# Power.net
KiCad netlist of a schematic drawn in Altium Designer
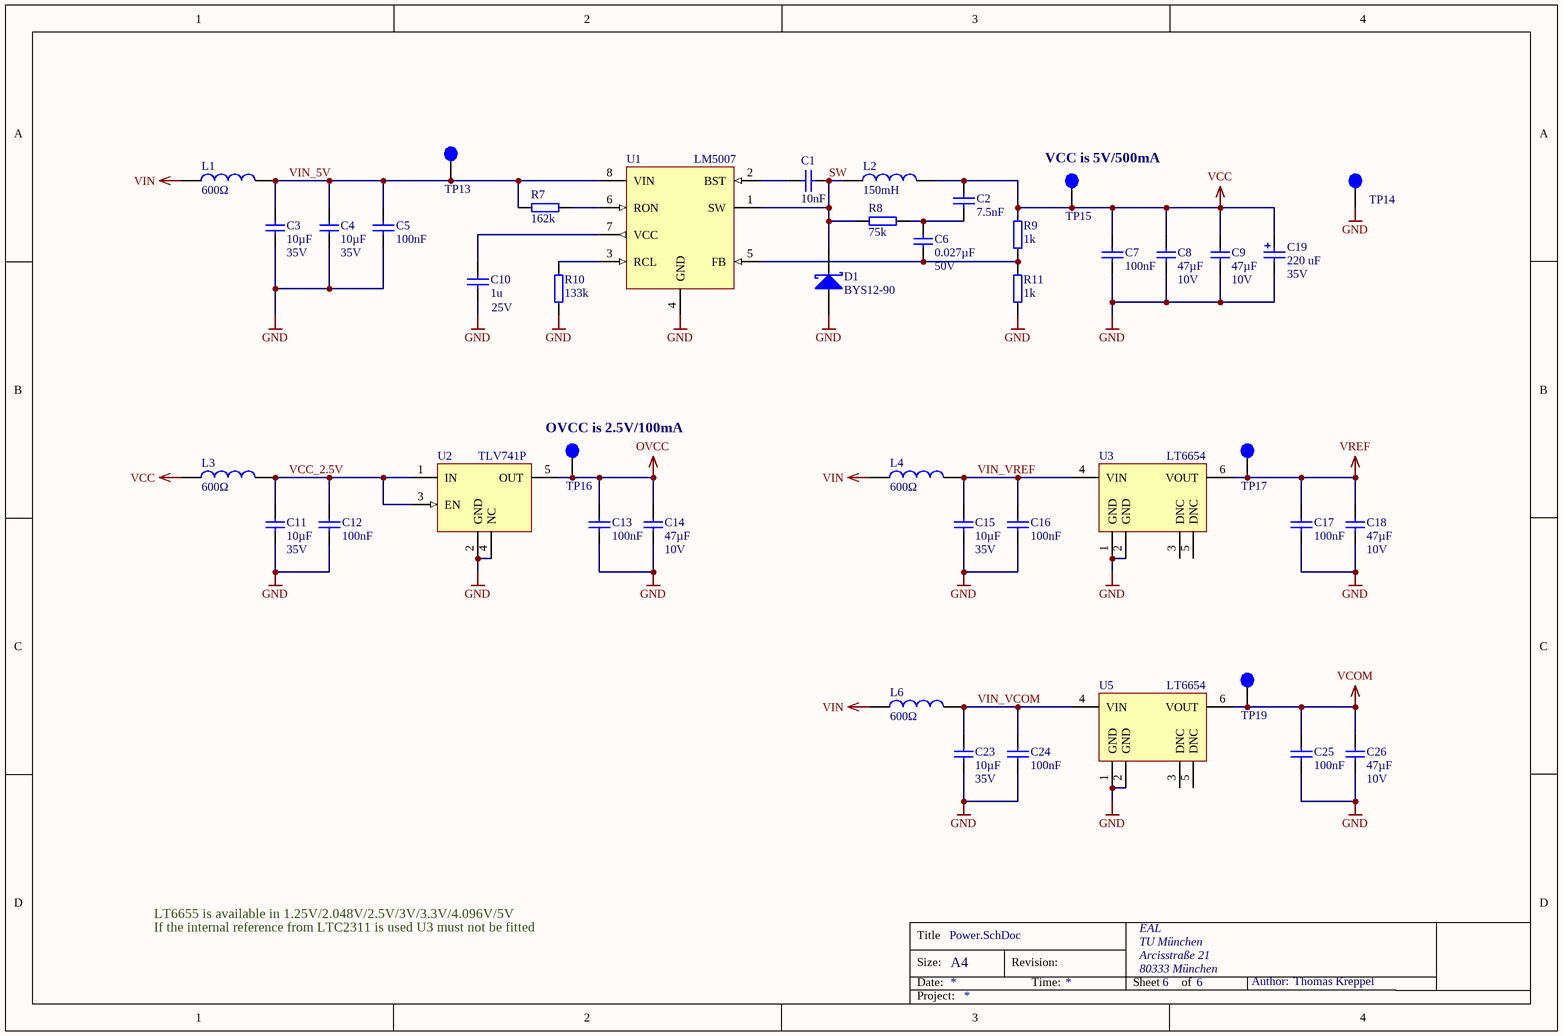
[diagram p0: Power.SchDoc]

(export (version "E")
  (design (tool "Eeschema 10.0.6"))
  (components
    (comp (ref "C1")
      (value "10nF")
      (footprint "CAPC1608X07N")
      (fields (field (name "MF") "Würth") (field (name "MPN") "885012206065") (field (name "VOLTAGE") "25V"))
      (libsource (lib "UltraZohm_ADC") (part "Cap_0603"))
    )
    (comp (ref "C2")
      (value "7.5nF")
      (footprint "CAPC1608X07N")
      (fields
        (field (name "MF") "KEMET")
        (field (name "MPN") "C0603C752J3GACTU")
        (field (name "VOLTAGE") "25V")
      )
      (libsource (lib "UltraZohm_ADC") (part "Cap_0603"))
    )
    (comp (ref "C3")
      (value "10µF")
      (footprint "C_1206")
      (description "Capacitor 1206")
      (fields
        (field (name "TOLERANCE") "10%")
        (field (name "MF") "Murata Electronics")
        (field (name "VOLTAGE") "35V")
        (field (name "CREATED") "2018_06_25_AGeiger")
      )
      (libsource (lib "UltraZohm_ADC") (part "C_1206"))
    )
    (comp (ref "C4")
      (value "10µF")
      (footprint "C_1206")
      (description "Capacitor 1206")
      (fields
        (field (name "TOLERANCE") "10%")
        (field (name "MF") "Murata Electronics")
        (field (name "VOLTAGE") "35V")
        (field (name "CREATED") "2018_06_25_AGeiger")
      )
      (libsource (lib "UltraZohm_ADC") (part "C_1206"))
    )
    (comp (ref "C5")
      (value "100nF")
      (footprint "CAPC1608X07N")
      (fields (field (name "MF") "Würth") (field (name "MPN") "885012206071") (field (name "VOLTAGE") "25V"))
      (libsource (lib "UltraZohm_ADC") (part "Cap_0603"))
    )
    (comp (ref "C6")
      (value "0.027µF")
      (footprint "C_1206")
      (description "Capacitor 1206")
      (fields
        (field (name "TOLERANCE") "5%")
        (field (name "MF") "Murata")
        (field (name "VOLTAGE") "50V")
        (field (name "CREATED") "2018_06_25_AGeiger")
      )
      (libsource (lib "UltraZohm_ADC") (part "C_1206"))
    )
    (comp (ref "C7")
      (value "100nF")
      (footprint "CAPC1608X07N")
      (fields (field (name "MF") "Würth") (field (name "MPN") "885012206071") (field (name "VOLTAGE") "25V"))
      (libsource (lib "UltraZohm_ADC") (part "Cap_0603"))
    )
    (comp (ref "C8")
      (value "47µF")
      (footprint "C_1206")
      (description "Capacitor 1206")
      (fields
        (field (name "TOLERANCE") "10%")
        (field (name "MF") "Murata Electronics")
        (field (name "VOLTAGE") "10V")
        (field (name "CREATED") "2018_06_25_AGeiger")
      )
      (libsource (lib "UltraZohm_ADC") (part "C_1206"))
    )
    (comp (ref "C9")
      (value "47µF")
      (footprint "C_1206")
      (description "Capacitor 1206")
      (fields
        (field (name "TOLERANCE") "10%")
        (field (name "MF") "Murata Electronics")
        (field (name "VOLTAGE") "10V")
        (field (name "CREATED") "2018_06_25_AGeiger")
      )
      (libsource (lib "UltraZohm_ADC") (part "C_1206"))
    )
    (comp (ref "C10")
      (value "1u")
      (footprint "CAPC1608X07N")
      (fields (field (name "MF") "Würth") (field (name "MPN") "885012106022") (field (name "VOLTAGE") "25V"))
      (libsource (lib "UltraZohm_ADC") (part "Cap_0603"))
    )
    (comp (ref "C11")
      (value "10µF")
      (footprint "C_1206")
      (description "Capacitor 1206")
      (fields
        (field (name "TOLERANCE") "10%")
        (field (name "MF") "Murata Electronics")
        (field (name "VOLTAGE") "35V")
        (field (name "CREATED") "2018_06_25_AGeiger")
      )
      (libsource (lib "UltraZohm_ADC") (part "C_1206"))
    )
    (comp (ref "C12")
      (value "100nF")
      (footprint "CAPC1608X07N")
      (fields (field (name "MF") "Würth") (field (name "MPN") "885012206071") (field (name "VOLTAGE") "25V"))
      (libsource (lib "UltraZohm_ADC") (part "Cap_0603"))
    )
    (comp (ref "C13")
      (value "100nF")
      (footprint "CAPC1608X07N")
      (fields (field (name "MF") "Würth") (field (name "MPN") "885012206071") (field (name "VOLTAGE") "25V"))
      (libsource (lib "UltraZohm_ADC") (part "Cap_0603"))
    )
    (comp (ref "C14")
      (value "47µF")
      (footprint "C_1206")
      (description "Capacitor 1206")
      (fields
        (field (name "TOLERANCE") "10%")
        (field (name "MF") "Murata Electronics")
        (field (name "VOLTAGE") "10V")
        (field (name "CREATED") "2018_06_25_AGeiger")
      )
      (libsource (lib "UltraZohm_ADC") (part "C_1206"))
    )
    (comp (ref "C15")
      (value "10µF")
      (footprint "C_1206")
      (description "Capacitor 1206")
      (fields
        (field (name "TOLERANCE") "10%")
        (field (name "MF") "Murata Electronics")
        (field (name "VOLTAGE") "35V")
        (field (name "CREATED") "2018_06_25_AGeiger")
      )
      (libsource (lib "UltraZohm_ADC") (part "C_1206"))
    )
    (comp (ref "C16")
      (value "100nF")
      (footprint "CAPC1608X07N")
      (fields (field (name "MF") "Würth") (field (name "MPN") "885012206071") (field (name "VOLTAGE") "25V"))
      (libsource (lib "UltraZohm_ADC") (part "Cap_0603"))
    )
    (comp (ref "C17")
      (value "100nF")
      (footprint "CAPC1608X07N")
      (fields (field (name "MF") "Würth") (field (name "MPN") "885012206071") (field (name "VOLTAGE") "25V"))
      (libsource (lib "UltraZohm_ADC") (part "Cap_0603"))
    )
    (comp (ref "C18")
      (value "47µF")
      (footprint "C_1206")
      (description "Capacitor 1206")
      (fields
        (field (name "TOLERANCE") "10%")
        (field (name "MF") "Murata Electronics")
        (field (name "VOLTAGE") "10V")
        (field (name "CREATED") "2018_06_25_AGeiger")
      )
      (libsource (lib "UltraZohm_ADC") (part "C_1206"))
    )
    (comp (ref "C19")
      (value "220 uF")
      (footprint "WCAP-ATG5_8x11.5x3.5")
      (description "WCAP-ATG5 Aluminum Electrolytic Capacitors, 8x11.5mm, 35 Vdc, 220 uF")
      (fields
        (field (name "PART NUMBER") "860020574012")
        (field (name "MF") "Wurth Elektronik")
        (field (name "VOLTAGE") "35V")
      )
      (libsource (lib "UltraZohm_ADC") (part "860020574012"))
    )
    (comp (ref "C23")
      (value "10µF")
      (footprint "C_1206")
      (description "Capacitor 1206")
      (fields
        (field (name "TOLERANCE") "10%")
        (field (name "MF") "Murata Electronics")
        (field (name "VOLTAGE") "35V")
        (field (name "CREATED") "2018_06_25_AGeiger")
      )
      (libsource (lib "UltraZohm_ADC") (part "C_1206"))
    )
    (comp (ref "C24")
      (value "100nF")
      (footprint "CAPC1608X07N")
      (fields (field (name "MF") "Würth") (field (name "MPN") "885012206071") (field (name "VOLTAGE") "25V"))
      (libsource (lib "UltraZohm_ADC") (part "Cap_0603"))
    )
    (comp (ref "C25")
      (value "100nF")
      (footprint "CAPC1608X07N")
      (fields (field (name "MF") "Würth") (field (name "MPN") "885012206071") (field (name "VOLTAGE") "25V"))
      (libsource (lib "UltraZohm_ADC") (part "Cap_0603"))
    )
    (comp (ref "C26")
      (value "47µF")
      (footprint "C_1206")
      (description "Capacitor 1206")
      (fields
        (field (name "TOLERANCE") "10%")
        (field (name "MF") "Murata Electronics")
        (field (name "VOLTAGE") "10V")
        (field (name "CREATED") "2018_06_25_AGeiger")
      )
      (libsource (lib "UltraZohm_ADC") (part "C_1206"))
    )
    (comp (ref "D1")
      (value "BYS12-90")
      (footprint "DIOM4227X23N")
      (description "Schottky Diode")
      (fields (field (name "MF") "Vishay") (field (name "MPN") "BYS12-90-E3/TR3"))
      (libsource (lib "UltraZohm_ADC") (part "BYS12-90"))
    )
    (comp (ref "L1")
      (value "600Ω")
      (footprint "WE-CBF_0805_High Current")
      (description "WE-CBF SMD EMI Suppression Ferrite Bead, 0805, 600Ω")
      (fields (field (name "MF") "Wurth Elektronik") (field (name "MPN") "742792040"))
      (libsource (lib "UltraZohm_ADC") (part "WE-CBF, 742792040"))
    )
    (comp (ref "L2")
      (value "150mH")
      (footprint "SMT_inductor_1050_Performance")
      (description "SMT power Inductor, 150uH, 320m DRC")
      (fields (field (name "MF") "EPCOS / TDK") (field (name "MPN") "B82464G4154M"))
      (libsource (lib "UltraZohm_ADC") (part "B82464G4154M"))
    )
    (comp (ref "L3")
      (value "600Ω")
      (footprint "WE-CBF_0805_High Current")
      (description "WE-CBF SMD EMI Suppression Ferrite Bead, 0805, 600Ω")
      (fields (field (name "MF") "Wurth Elektronik") (field (name "MPN") "742792040"))
      (libsource (lib "UltraZohm_ADC") (part "WE-CBF, 742792040"))
    )
    (comp (ref "L4")
      (value "600Ω")
      (footprint "WE-CBF_0805_High Current")
      (description "WE-CBF SMD EMI Suppression Ferrite Bead, 0805, 600Ω")
      (fields (field (name "MF") "Wurth Elektronik") (field (name "MPN") "742792040"))
      (libsource (lib "UltraZohm_ADC") (part "WE-CBF, 742792040"))
    )
    (comp (ref "L6")
      (value "600Ω")
      (footprint "WE-CBF_0805_High Current")
      (description "WE-CBF SMD EMI Suppression Ferrite Bead, 0805, 600Ω")
      (fields (field (name "MF") "Wurth Elektronik") (field (name "MPN") "742792040"))
      (libsource (lib "UltraZohm_ADC") (part "WE-CBF, 742792040"))
    )
    (comp (ref "R7")
      (value "162k")
      (footprint "RESC1608X06N")
      (fields (field (name "MF") "Bourns") (field (name "MPN") "CR0603-FX-1623ELF"))
      (libsource (lib "UltraZohm_ADC") (part "R_0603"))
    )
    (comp (ref "R8")
      (value "75k")
      (footprint "RESC1608X06N")
      (fields (field (name "MF") "Yageo") (field (name "MPN") "AC0603FR-1375KL"))
      (libsource (lib "UltraZohm_ADC") (part "R_0603"))
    )
    (comp (ref "R9")
      (value "1k")
      (footprint "RESC1608X06N")
      (fields (field (name "MF") "Vishay / Dale") (field (name "MPN") "CRCW06031K00JNEAC"))
      (libsource (lib "UltraZohm_ADC") (part "R_0603"))
    )
    (comp (ref "R10")
      (value "133k")
      (footprint "RESC1608X06N")
      (fields (field (name "MF") "Bourns") (field (name "MPN") "CR0603-FX-1333ELF"))
      (libsource (lib "UltraZohm_ADC") (part "R_0603"))
    )
    (comp (ref "R11")
      (value "1k")
      (footprint "RESC1608X06N")
      (fields (field (name "MF") "Vishay / Dale") (field (name "MPN") "CRCW06031K00JNEAC"))
      (libsource (lib "UltraZohm_ADC") (part "R_0603"))
    )
    (comp (ref "TP13")
      (value "VIN")
      (footprint "TP_1mm")
      (description "Testpoint 1mm")
      (fields (field (name "CREATED") "2018_06_25_AGeiger"))
      (libsource (lib "UltraZOhm_CarrierBoard") (part "TP_1mm"))
    )
    (comp (ref "TP14")
      (value "GND")
      (footprint "TP_1mm")
      (description "Testpoint 1mm")
      (fields (field (name "CREATED") "2018_06_25_AGeiger"))
      (libsource (lib "UltraZOhm_CarrierBoard") (part "TP_1mm"))
    )
    (comp (ref "TP15")
      (value "VCC")
      (footprint "TP_1mm")
      (description "Testpoint 1mm")
      (fields (field (name "CREATED") "2018_06_25_AGeiger"))
      (libsource (lib "UltraZOhm_CarrierBoard") (part "TP_1mm"))
    )
    (comp (ref "TP16")
      (value "OVCC")
      (footprint "TP_1mm")
      (description "Testpoint 1mm")
      (fields (field (name "CREATED") "2018_06_25_AGeiger"))
      (libsource (lib "UltraZOhm_CarrierBoard") (part "TP_1mm"))
    )
    (comp (ref "TP17")
      (value "VREF")
      (footprint "TP_1mm")
      (description "Testpoint 1mm")
      (fields (field (name "CREATED") "2018_06_25_AGeiger"))
      (libsource (lib "UltraZOhm_CarrierBoard") (part "TP_1mm"))
    )
    (comp (ref "TP19")
      (value "VCOM")
      (footprint "TP_1mm")
      (description "Testpoint 1mm")
      (fields (field (name "CREATED") "2018_06_25_AGeiger"))
      (libsource (lib "UltraZOhm_CarrierBoard") (part "TP_1mm"))
    )
    (comp (ref "U1")
      (value "LM5007")
      (footprint "TSOP65P490X110-8N")
      (description "Buck Converter, 9-75Vin, 2.5-73Vout")
      (fields (field (name "MF") "Texas Instruments") (field (name "MPN") "LM5007MM/NOPB"))
      (libsource (lib "UltraZohm_ADC") (part "LM5007"))
    )
    (comp (ref "U2")
      (value "TLV741P")
      (footprint "SOT95P250X110-5N")
      (description "150mA, 2.5V LDO")
      (fields (field (name "MF") "Texas Instruments") (field (name "MPN") "TLV74125PDBVR"))
      (libsource (lib "UltraZohm_ADC") (part "TLV741P"))
    )
    (comp (ref "U3")
      (value "LT6654")
      (footprint "SOT95P280X100-6N")
      (fields (field (name "MF") "Analog Devices") (field (name "MPN") "LT6654AIS6-5#TRMPBF"))
      (libsource (lib "UltraZohm_ADC") (part "LT6654"))
    )
    (comp (ref "U5")
      (value "LT6654")
      (footprint "SOT95P280X100-6N")
      (fields (field (name "MF") "Analog Devices") (field (name "MPN") "LT6654AIS6-5#TRMPBF"))
      (libsource (lib "UltraZohm_ADC") (part "LT6654"))
    )
  )
  (nets
    (net (code "1") (name "/SW") (class "Default")
      (node (ref "C1") (pin "2") (pinfunction "2_2") (pintype "passive"))
      (node (ref "D1") (pin "1") (pinfunction "K_1") (pintype "passive"))
      (node (ref "L2") (pin "1") (pinfunction "1_1") (pintype "passive"))
      (node (ref "R8") (pin "1") (pintype "passive"))
      (node (ref "U1") (pin "1") (pinfunction "SW_1") (pintype "power_in"))
    )
    (net (code "2") (name "/VCC_2.5V") (class "Default")
      (node (ref "C11") (pin "2") (pinfunction "2_2") (pintype "passive"))
      (node (ref "C12") (pin "1") (pinfunction "1_1") (pintype "passive"))
      (node (ref "L3") (pin "2") (pinfunction "2_2") (pintype "passive"))
      (node (ref "U2") (pin "1") (pinfunction "IN_1") (pintype "power_in"))
      (node (ref "U2") (pin "3") (pinfunction "EN_3") (pintype "input"))
    )
    (net (code "3") (name "/VIN_5V") (class "Default")
      (node (ref "C3") (pin "2") (pinfunction "2_2") (pintype "passive"))
      (node (ref "C4") (pin "2") (pinfunction "2_2") (pintype "passive"))
      (node (ref "C5") (pin "1") (pinfunction "1_1") (pintype "passive"))
      (node (ref "L1") (pin "2") (pinfunction "2_2") (pintype "passive"))
      (node (ref "R7") (pin "1") (pintype "passive"))
      (node (ref "TP13") (pin "1") (pintype "passive"))
      (node (ref "U1") (pin "8") (pinfunction "VIN_8") (pintype "power_in"))
    )
    (net (code "4") (name "/VIN_VCOM") (class "Default")
      (node (ref "C23") (pin "2") (pinfunction "2_2") (pintype "passive"))
      (node (ref "C24") (pin "1") (pinfunction "1_1") (pintype "passive"))
      (node (ref "L6") (pin "2") (pinfunction "2_2") (pintype "passive"))
      (node (ref "U5") (pin "4") (pinfunction "VIN_4") (pintype "power_in"))
    )
    (net (code "5") (name "/VIN_VREF") (class "Default")
      (node (ref "C15") (pin "2") (pinfunction "2_2") (pintype "passive"))
      (node (ref "C16") (pin "1") (pinfunction "1_1") (pintype "passive"))
      (node (ref "L4") (pin "2") (pinfunction "2_2") (pintype "passive"))
      (node (ref "U3") (pin "4") (pinfunction "VIN_4") (pintype "power_in"))
    )
    (net (code "6") (name "GND") (class "Default")
      (node (ref "C10") (pin "2") (pinfunction "2_2") (pintype "passive"))
      (node (ref "C11") (pin "1") (pinfunction "1_1") (pintype "passive"))
      (node (ref "C12") (pin "2") (pinfunction "2_2") (pintype "passive"))
      (node (ref "C13") (pin "2") (pinfunction "2_2") (pintype "passive"))
      (node (ref "C14") (pin "1") (pinfunction "1_1") (pintype "passive"))
      (node (ref "C15") (pin "1") (pinfunction "1_1") (pintype "passive"))
      (node (ref "C16") (pin "2") (pinfunction "2_2") (pintype "passive"))
      (node (ref "C17") (pin "2") (pinfunction "2_2") (pintype "passive"))
      (node (ref "C18") (pin "1") (pinfunction "1_1") (pintype "passive"))
      (node (ref "C19") (pin "2") (pinfunction "N_2") (pintype "passive"))
      (node (ref "C23") (pin "1") (pinfunction "1_1") (pintype "passive"))
      (node (ref "C24") (pin "2") (pinfunction "2_2") (pintype "passive"))
      (node (ref "C25") (pin "2") (pinfunction "2_2") (pintype "passive"))
      (node (ref "C26") (pin "1") (pinfunction "1_1") (pintype "passive"))
      (node (ref "C3") (pin "1") (pinfunction "1_1") (pintype "passive"))
      (node (ref "C4") (pin "1") (pinfunction "1_1") (pintype "passive"))
      (node (ref "C5") (pin "2") (pinfunction "2_2") (pintype "passive"))
      (node (ref "C7") (pin "1") (pinfunction "1_1") (pintype "passive"))
      (node (ref "C8") (pin "1") (pinfunction "1_1") (pintype "passive"))
      (node (ref "C9") (pin "1") (pinfunction "1_1") (pintype "passive"))
      (node (ref "D1") (pin "2") (pinfunction "A_2") (pintype "passive"))
      (node (ref "R10") (pin "1") (pintype "passive"))
      (node (ref "R11") (pin "1") (pintype "passive"))
      (node (ref "TP14") (pin "1") (pintype "passive"))
      (node (ref "U1") (pin "4") (pinfunction "GND_4") (pintype "power_in"))
      (node (ref "U2") (pin "2") (pinfunction "GND_2") (pintype "power_in"))
      (node (ref "U2") (pin "4") (pinfunction "NC_4") (pintype "passive"))
      (node (ref "U3") (pin "1") (pinfunction "GND_1") (pintype "power_in"))
      (node (ref "U3") (pin "2") (pinfunction "GND_2") (pintype "power_in"))
      (node (ref "U5") (pin "1") (pinfunction "GND_1") (pintype "power_in"))
      (node (ref "U5") (pin "2") (pinfunction "GND_2") (pintype "power_in"))
    )
    (net (code "7") (name "Net-(C2-Pad2)") (class "Default")
      (node (ref "C2") (pin "2") (pinfunction "2_2") (pintype "passive"))
      (node (ref "C6") (pin "2") (pinfunction "2_2") (pintype "passive"))
      (node (ref "R8") (pin "2") (pintype "passive"))
    )
    (net (code "8") (name "Net-(U1-BST)") (class "Default")
      (node (ref "C1") (pin "1") (pinfunction "1_1") (pintype "passive"))
      (node (ref "U1") (pin "2") (pinfunction "BST_2") (pintype "input"))
    )
    (net (code "9") (name "Net-(U1-FB)") (class "Default")
      (node (ref "C6") (pin "1") (pinfunction "1_1") (pintype "passive"))
      (node (ref "R11") (pin "2") (pintype "passive"))
      (node (ref "R9") (pin "1") (pintype "passive"))
      (node (ref "U1") (pin "5") (pinfunction "FB_5") (pintype "input"))
    )
    (net (code "10") (name "Net-(U1-RCL)") (class "Default")
      (node (ref "R10") (pin "2") (pintype "passive"))
      (node (ref "U1") (pin "3") (pinfunction "RCL_3") (pintype "input"))
    )
    (net (code "11") (name "Net-(U1-RON)") (class "Default")
      (node (ref "R7") (pin "2") (pintype "passive"))
      (node (ref "U1") (pin "6") (pinfunction "RON_6") (pintype "input"))
    )
    (net (code "12") (name "Net-(U1-VCC)") (class "Default")
      (node (ref "C10") (pin "1") (pinfunction "1_1") (pintype "passive"))
      (node (ref "U1") (pin "7") (pinfunction "VCC_7") (pintype "output"))
    )
    (net (code "13") (name "OVCC") (class "Default")
      (node (ref "C13") (pin "1") (pinfunction "1_1") (pintype "passive"))
      (node (ref "C14") (pin "2") (pinfunction "2_2") (pintype "passive"))
      (node (ref "TP16") (pin "1") (pintype "passive"))
      (node (ref "U2") (pin "5") (pinfunction "OUT_5") (pintype "power_in"))
    )
    (net (code "14") (name "VCC") (class "Default")
      (node (ref "C19") (pin "1") (pinfunction "P_1") (pintype "passive"))
      (node (ref "C2") (pin "1") (pinfunction "1_1") (pintype "passive"))
      (node (ref "C7") (pin "2") (pinfunction "2_2") (pintype "passive"))
      (node (ref "C8") (pin "2") (pinfunction "2_2") (pintype "passive"))
      (node (ref "C9") (pin "2") (pinfunction "2_2") (pintype "passive"))
      (node (ref "L2") (pin "2") (pinfunction "2_2") (pintype "passive"))
      (node (ref "L3") (pin "1") (pinfunction "1_1") (pintype "passive"))
      (node (ref "R9") (pin "2") (pintype "passive"))
      (node (ref "TP15") (pin "1") (pintype "passive"))
    )
    (net (code "15") (name "VCOM") (class "Default")
      (node (ref "C25") (pin "1") (pinfunction "1_1") (pintype "passive"))
      (node (ref "C26") (pin "2") (pinfunction "2_2") (pintype "passive"))
      (node (ref "TP19") (pin "1") (pintype "passive"))
      (node (ref "U5") (pin "6") (pinfunction "VOUT_6") (pintype "power_in"))
    )
    (net (code "16") (name "VIN") (class "Default")
      (node (ref "L1") (pin "1") (pinfunction "1_1") (pintype "passive"))
      (node (ref "L4") (pin "1") (pinfunction "1_1") (pintype "passive"))
      (node (ref "L6") (pin "1") (pinfunction "1_1") (pintype "passive"))
    )
    (net (code "17") (name "VREF") (class "Default")
      (node (ref "C17") (pin "1") (pinfunction "1_1") (pintype "passive"))
      (node (ref "C18") (pin "2") (pinfunction "2_2") (pintype "passive"))
      (node (ref "TP17") (pin "1") (pintype "passive"))
      (node (ref "U3") (pin "6") (pinfunction "VOUT_6") (pintype "power_in"))
    )
    (net (code "18") (name "unconnected-(U3-DNC-Pad3)") (class "Default")
      (node (ref "U3") (pin "3") (pinfunction "DNC_3") (pintype "passive"))
    )
    (net (code "19") (name "unconnected-(U3-DNC-Pad5)") (class "Default")
      (node (ref "U3") (pin "5") (pinfunction "DNC_5") (pintype "passive"))
    )
    (net (code "20") (name "unconnected-(U5-DNC-Pad3)") (class "Default")
      (node (ref "U5") (pin "3") (pinfunction "DNC_3") (pintype "passive"))
    )
    (net (code "21") (name "unconnected-(U5-DNC-Pad5)") (class "Default")
      (node (ref "U5") (pin "5") (pinfunction "DNC_5") (pintype "passive"))
    )
  )
)
